# telemetry_box.net
KiCad netlist of a schematic drawn in EAGLE
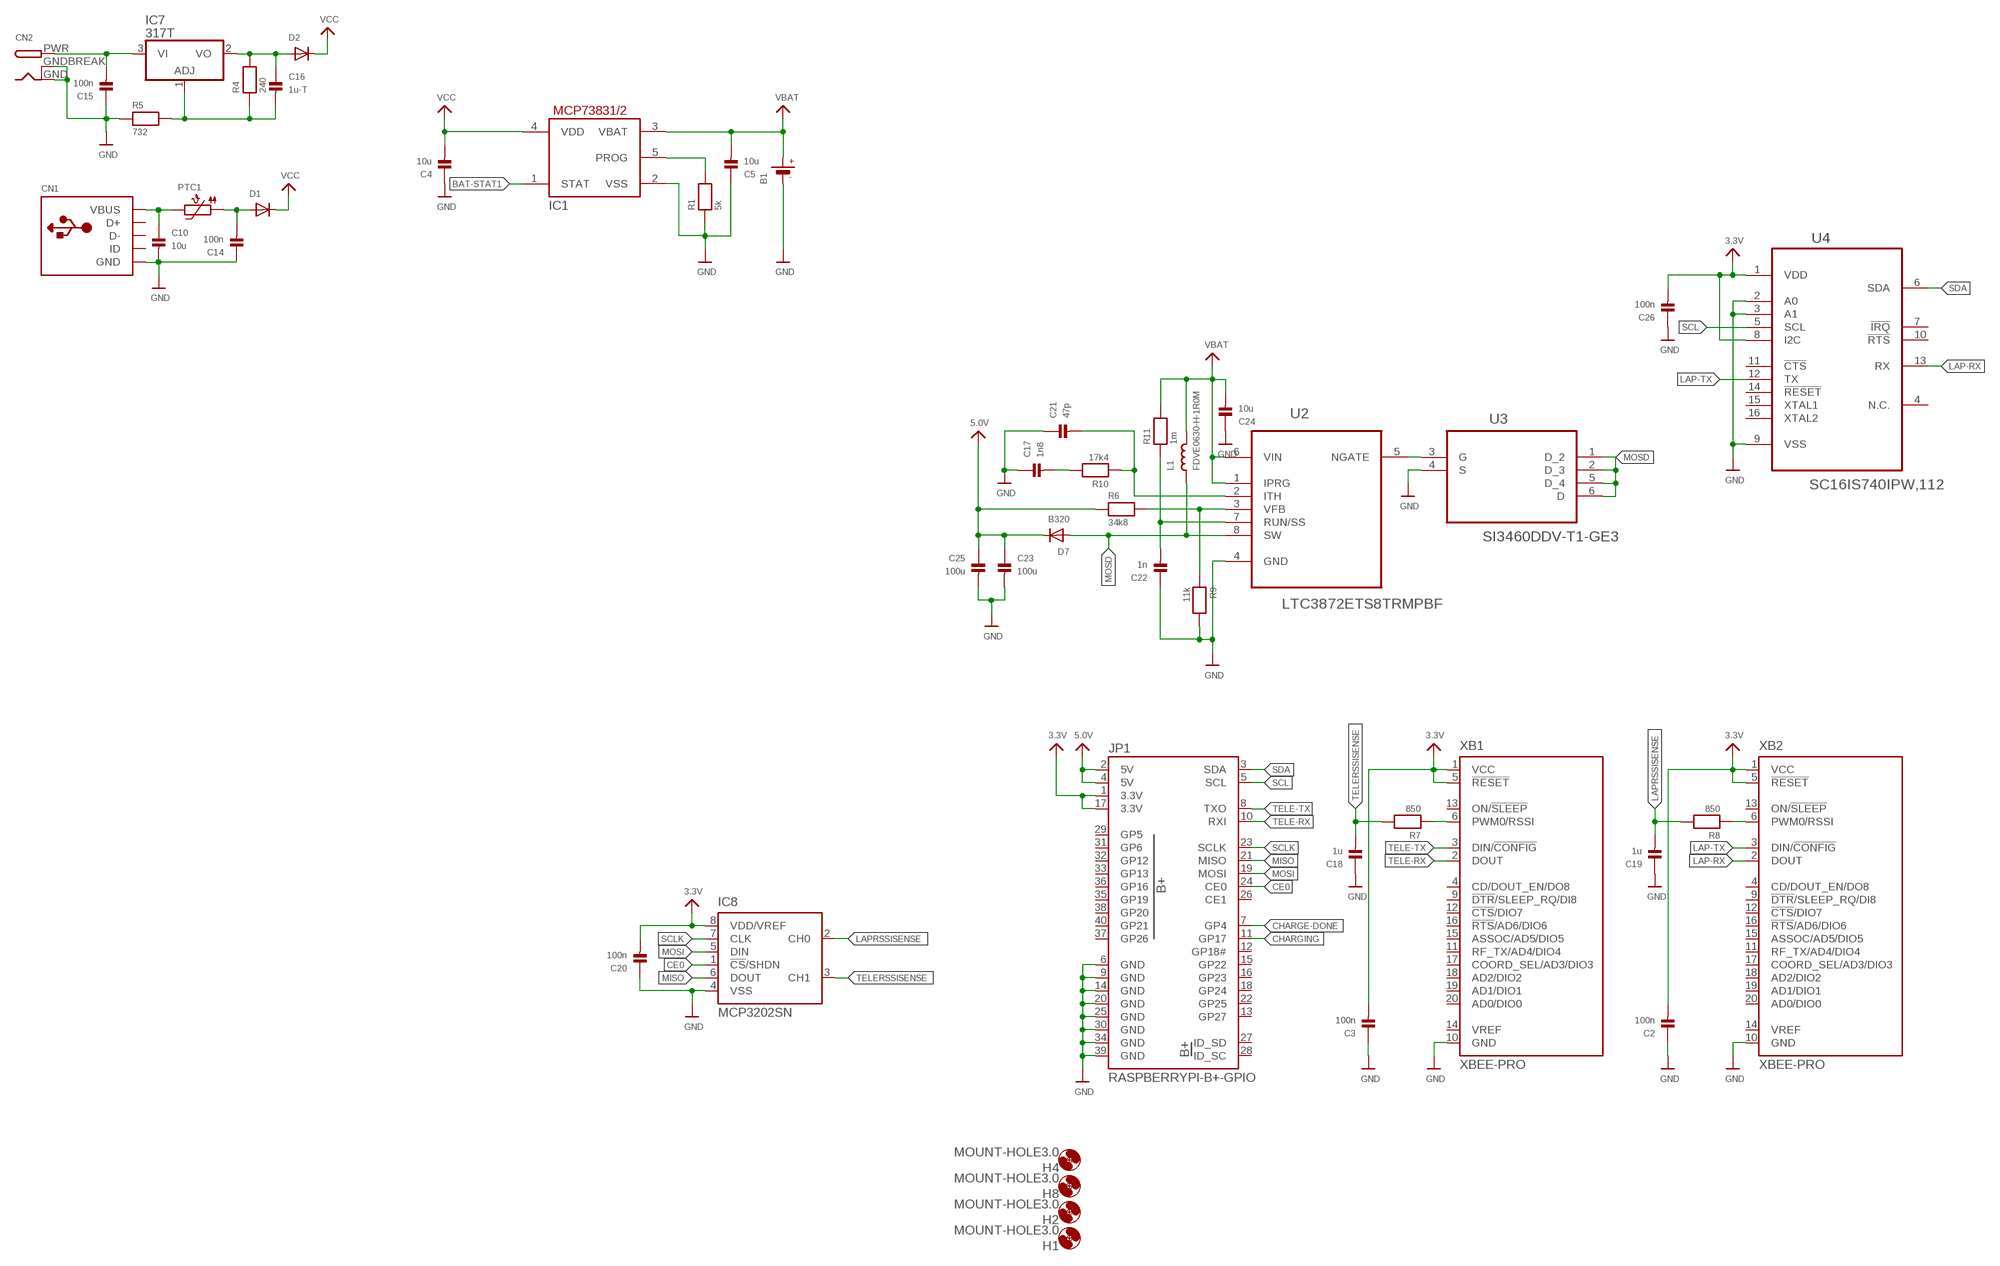
[diagram p0: schematic, sheet 1]

(export (version "E")
  (design (tool "Eeschema 10.0.6"))
  (components
    (comp (ref "B1")
      (value "BATTERY")
      (footprint "eagle-import:JSTPH2")
      (libsource (lib "eagle-import") (part "BATTERY"))
    )
    (comp (ref "C2")
      (value "100n")
      (footprint "eagle-import:_0603")
      (libsource (lib "eagle-import") (part "CAP_CERAMIC_0603"))
    )
    (comp (ref "C3")
      (value "100n")
      (footprint "eagle-import:_0603")
      (libsource (lib "eagle-import") (part "CAP_CERAMIC_0603"))
    )
    (comp (ref "C4")
      (value "10u")
      (footprint "eagle-import:_0805")
      (libsource (lib "eagle-import") (part "CAP_CERAMIC_0805"))
    )
    (comp (ref "C5")
      (value "10u")
      (footprint "eagle-import:_0805")
      (libsource (lib "eagle-import") (part "CAP_CERAMIC_0805"))
    )
    (comp (ref "C10")
      (value "10u")
      (footprint "eagle-import:_0805")
      (libsource (lib "eagle-import") (part "CAP_CERAMIC_0805"))
    )
    (comp (ref "C14")
      (value "100n")
      (footprint "eagle-import:_0603")
      (libsource (lib "eagle-import") (part "CAP_CERAMIC_0603"))
    )
    (comp (ref "C15")
      (value "100n")
      (footprint "eagle-import:_0603")
      (libsource (lib "eagle-import") (part "CAP_CERAMIC_0603"))
    )
    (comp (ref "C16")
      (value "1u-T")
      (footprint "eagle-import:_0603")
      (libsource (lib "eagle-import") (part "CAP_CERAMIC_0603"))
    )
    (comp (ref "C17")
      (value "1n8")
      (footprint "eagle-import:_0603")
      (libsource (lib "eagle-import") (part "CAP_CERAMIC_0603"))
    )
    (comp (ref "C18")
      (value "1u")
      (footprint "eagle-import:_0603")
      (libsource (lib "eagle-import") (part "CAP_CERAMIC_0603"))
    )
    (comp (ref "C19")
      (value "1u")
      (footprint "eagle-import:_0603")
      (libsource (lib "eagle-import") (part "CAP_CERAMIC_0603"))
    )
    (comp (ref "C20")
      (value "100n")
      (footprint "eagle-import:_0603")
      (libsource (lib "eagle-import") (part "CAP_CERAMIC_0603"))
    )
    (comp (ref "C21")
      (value "47p")
      (footprint "eagle-import:_0603")
      (libsource (lib "eagle-import") (part "CAP_CERAMIC_0603"))
    )
    (comp (ref "C22")
      (value "1n")
      (footprint "eagle-import:_0603")
      (libsource (lib "eagle-import") (part "CAP_CERAMIC_0603"))
    )
    (comp (ref "C23")
      (value "100u")
      (footprint "eagle-import:1206")
      (libsource (lib "eagle-import") (part "CAP_CERAMIC1206"))
    )
    (comp (ref "C24")
      (value "10u")
      (footprint "eagle-import:_0805")
      (libsource (lib "eagle-import") (part "CAP_CERAMIC_0805"))
    )
    (comp (ref "C25")
      (value "100u")
      (footprint "eagle-import:1206")
      (libsource (lib "eagle-import") (part "CAP_CERAMIC1206"))
    )
    (comp (ref "C26")
      (value "100n")
      (footprint "eagle-import:_0603")
      (libsource (lib "eagle-import") (part "CAP_CERAMIC_0603"))
    )
    (comp (ref "CN1")
      (value "USBMINIB")
      (footprint "eagle-import:USB-MINIB")
      (libsource (lib "eagle-import") (part "USBMINIB"))
    )
    (comp (ref "CN2")
      (value "DCBARRELPTH")
      (footprint "eagle-import:DCJACK_2MM_PTH")
      (libsource (lib "eagle-import") (part "DCBARRELPTH"))
    )
    (comp (ref "D1")
      (value "DIODESOT23_WAVE")
      (footprint "eagle-import:SOT23-W")
      (libsource (lib "eagle-import") (part "DIODESOT23_WAVE"))
    )
    (comp (ref "D2")
      (value "DIODESOT23_WAVE")
      (footprint "eagle-import:SOT23-W")
      (libsource (lib "eagle-import") (part "DIODESOT23_WAVE"))
    )
    (comp (ref "D7")
      (value "B320")
      (footprint "eagle-import:SMADIODE")
      (libsource (lib "eagle-import") (part "DIODESMA"))
    )
    (comp (ref "H1")
      (value "MOUNT-HOLE3.0")
      (footprint "eagle-import:3,0")
      (libsource (lib "eagle-import") (part "MOUNT-HOLE3.0"))
    )
    (comp (ref "H2")
      (value "MOUNT-HOLE3.0")
      (footprint "eagle-import:3,0")
      (libsource (lib "eagle-import") (part "MOUNT-HOLE3.0"))
    )
    (comp (ref "H4")
      (value "MOUNT-HOLE3.0")
      (footprint "eagle-import:3,0")
      (libsource (lib "eagle-import") (part "MOUNT-HOLE3.0"))
    )
    (comp (ref "H8")
      (value "MOUNT-HOLE3.0")
      (footprint "eagle-import:3,0")
      (libsource (lib "eagle-import") (part "MOUNT-HOLE3.0"))
    )
    (comp (ref "IC1")
      (value "MCP73831/OT")
      (footprint "eagle-import:SOT23-5L")
      (libsource (lib "eagle-import") (part "MCP73831/OT"))
    )
    (comp (ref "IC7")
      (value "317T")
      (footprint "eagle-import:TO220H")
      (libsource (lib "eagle-import") (part "317T"))
    )
    (comp (ref "IC8")
      (value "MCP3202SN")
      (footprint "eagle-import:SO-08")
      (fields (field (name "MF") "MICROCHIP") (field (name "MPN") "MCP3202-CI/SN"))
      (libsource (lib "eagle-import") (part "MCP3202SN"))
    )
    (comp (ref "JP1")
      (value "RASPBERRYPI-B+-GPIO")
      (footprint "eagle-import:2X20-SHROUDED")
      (libsource (lib "eagle-import") (part "RASPBERRYPI-B+-GPIO"))
    )
    (comp (ref "L1")
      (value "FDVE0630-H-1R0M")
      (footprint "eagle-import:INDUCTOR_6X6MM_TDK_SLF6045")
      (libsource (lib "eagle-import") (part "INDUCTORTDK_SLF6045"))
    )
    (comp (ref "PTC1")
      (value "PTC1206")
      (footprint "eagle-import:1206")
      (libsource (lib "eagle-import") (part "PTC1206"))
    )
    (comp (ref "R1")
      (value "5k")
      (footprint "eagle-import:_0603")
      (libsource (lib "eagle-import") (part "RESISTOR_0603"))
    )
    (comp (ref "R4")
      (value "240")
      (footprint "eagle-import:_0603")
      (libsource (lib "eagle-import") (part "RESISTOR_0603"))
    )
    (comp (ref "R5")
      (value "732")
      (footprint "eagle-import:_0603")
      (libsource (lib "eagle-import") (part "RESISTOR_0603"))
    )
    (comp (ref "R6")
      (value "34k8")
      (footprint "eagle-import:_0603")
      (libsource (lib "eagle-import") (part "RESISTOR_0603"))
    )
    (comp (ref "R7")
      (value "850")
      (footprint "eagle-import:_0603")
      (libsource (lib "eagle-import") (part "RESISTOR_0603"))
    )
    (comp (ref "R8")
      (value "850")
      (footprint "eagle-import:_0603")
      (libsource (lib "eagle-import") (part "RESISTOR_0603"))
    )
    (comp (ref "R9")
      (value "11k")
      (footprint "eagle-import:_0603")
      (libsource (lib "eagle-import") (part "RESISTOR_0603"))
    )
    (comp (ref "R10")
      (value "17k4")
      (footprint "eagle-import:_0603")
      (libsource (lib "eagle-import") (part "RESISTOR_0603"))
    )
    (comp (ref "R11")
      (value "1m")
      (footprint "eagle-import:_0603")
      (libsource (lib "eagle-import") (part "RESISTOR_0603"))
    )
    (comp (ref "U2")
      (value "LTC3872ETS8TRMPBF")
      (footprint "eagle-import:SOT65P280X100-8N")
      (fields (field (name "MPN") "LTC3872ETS8#TRMPBF"))
      (libsource (lib "eagle-import") (part "LTC3872ETS8TRMPBF"))
    )
    (comp (ref "U3")
      (value "SI3460DDV-T1-GE3")
      (footprint "eagle-import:SOT95P285X110-6N")
      (fields (field (name "MPN") "SI3457CDV-T1-GE3"))
      (libsource (lib "eagle-import") (part "SI3457CDV-T1-GE3"))
    )
    (comp (ref "U4")
      (value "SC16IS740IPW,112")
      (footprint "eagle-import:SOP65P640X110-16N")
      (libsource (lib "eagle-import") (part "SC16IS740IPW,112"))
    )
    (comp (ref "XB1")
      (value "XBEE-PRO")
      (footprint "eagle-import:XBEE-PRO")
      (libsource (lib "eagle-import") (part "XBEE-PRO"))
    )
    (comp (ref "XB2")
      (value "XBEE-PRO")
      (footprint "eagle-import:XBEE-PRO")
      (libsource (lib "eagle-import") (part "XBEE-PRO"))
    )
  )
  (nets
    (net (code "1") (name "3.3V") (class "Default")
      (node (ref "C2") (pin "2") (pinfunction "P$2_2") (pintype "passive"))
      (node (ref "C20") (pin "2") (pinfunction "P$2_2") (pintype "passive"))
      (node (ref "C26") (pin "2") (pinfunction "P$2_2") (pintype "passive"))
      (node (ref "C3") (pin "2") (pinfunction "P$2_2") (pintype "passive"))
      (node (ref "IC8") (pin "8") (pinfunction "VDD/VREF_8") (pintype "input"))
      (node (ref "JP1") (pin "1") (pinfunction "3.3V_1") (pintype "power_in"))
      (node (ref "JP1") (pin "17") (pinfunction "3.3V_17") (pintype "power_in"))
      (node (ref "U4") (pin "1") (pinfunction "VDD_1") (pintype "power_in"))
      (node (ref "U4") (pin "8") (pinfunction "I2C_8") (pintype "input"))
      (node (ref "XB1") (pin "1") (pinfunction "VCC_1") (pintype "power_in"))
      (node (ref "XB1") (pin "5") (pinfunction "~{RESET}_5") (pintype "input"))
      (node (ref "XB2") (pin "1") (pinfunction "VCC_1") (pintype "power_in"))
      (node (ref "XB2") (pin "5") (pinfunction "~{RESET}_5") (pintype "input"))
    )
    (net (code "2") (name "5.0V") (class "Default")
      (node (ref "C23") (pin "1") (pinfunction "P$1_1") (pintype "passive"))
      (node (ref "C25") (pin "1") (pinfunction "P$1_1") (pintype "passive"))
      (node (ref "D7") (pin "C") (pinfunction "C_C") (pintype "passive"))
      (node (ref "JP1") (pin "2") (pinfunction "5V_2") (pintype "power_in"))
      (node (ref "JP1") (pin "4") (pinfunction "5V_4") (pintype "power_in"))
      (node (ref "R6") (pin "1") (pinfunction "1_1") (pintype "passive"))
    )
    (net (code "3") (name "BAT-STAT1") (class "Default")
      (node (ref "IC1") (pin "1") (pinfunction "STAT_1") (pintype "output"))
    )
    (net (code "4") (name "CE0") (class "Default")
      (node (ref "IC8") (pin "1") (pinfunction "~{CS}/SHDN_1") (pintype "input"))
      (node (ref "JP1") (pin "24") (pinfunction "CE0_24") (pintype "output"))
    )
    (net (code "5") (name "CHARGE-DONE") (class "Default")
      (node (ref "JP1") (pin "7") (pinfunction "GP4_7") (pintype "bidirectional"))
    )
    (net (code "6") (name "CHARGING") (class "Default")
      (node (ref "JP1") (pin "11") (pinfunction "GP17_11") (pintype "bidirectional"))
    )
    (net (code "7") (name "GND") (class "Default")
      (node (ref "B1") (pin "1") (pinfunction "-_1") (pintype "passive"))
      (node (ref "C10") (pin "2") (pinfunction "P$2_2") (pintype "passive"))
      (node (ref "C14") (pin "1") (pinfunction "P$1_1") (pintype "passive"))
      (node (ref "C15") (pin "1") (pinfunction "P$1_1") (pintype "passive"))
      (node (ref "C17") (pin "1") (pinfunction "P$1_1") (pintype "passive"))
      (node (ref "C18") (pin "1") (pinfunction "P$1_1") (pintype "passive"))
      (node (ref "C19") (pin "1") (pinfunction "P$1_1") (pintype "passive"))
      (node (ref "C2") (pin "1") (pinfunction "P$1_1") (pintype "passive"))
      (node (ref "C20") (pin "1") (pinfunction "P$1_1") (pintype "passive"))
      (node (ref "C21") (pin "1") (pinfunction "P$1_1") (pintype "passive"))
      (node (ref "C22") (pin "1") (pinfunction "P$1_1") (pintype "passive"))
      (node (ref "C23") (pin "2") (pinfunction "P$2_2") (pintype "passive"))
      (node (ref "C24") (pin "1") (pinfunction "P$1_1") (pintype "passive"))
      (node (ref "C25") (pin "2") (pinfunction "P$2_2") (pintype "passive"))
      (node (ref "C26") (pin "1") (pinfunction "P$1_1") (pintype "passive"))
      (node (ref "C3") (pin "1") (pinfunction "P$1_1") (pintype "passive"))
      (node (ref "C4") (pin "1") (pinfunction "P$1_1") (pintype "passive"))
      (node (ref "C5") (pin "1") (pinfunction "P$1_1") (pintype "passive"))
      (node (ref "CN1") (pin "GND") (pinfunction "GND_GND") (pintype "power_in"))
      (node (ref "CN2") (pin "GND") (pinfunction "GND_GND") (pintype "power_in"))
      (node (ref "CN2") (pin "GNDBREAK") (pinfunction "GNDBREAK_GNDBREAK") (pintype "power_in"))
      (node (ref "IC1") (pin "2") (pinfunction "VSS_2") (pintype "power_in"))
      (node (ref "IC8") (pin "4") (pinfunction "VSS_4") (pintype "input"))
      (node (ref "JP1") (pin "14") (pinfunction "GND_14") (pintype "power_in"))
      (node (ref "JP1") (pin "20") (pinfunction "GND_20") (pintype "power_in"))
      (node (ref "JP1") (pin "25") (pinfunction "GND_25") (pintype "power_in"))
      (node (ref "JP1") (pin "30") (pinfunction "GND_30") (pintype "power_in"))
      (node (ref "JP1") (pin "34") (pinfunction "GND_34") (pintype "power_in"))
      (node (ref "JP1") (pin "39") (pinfunction "GND_39") (pintype "power_in"))
      (node (ref "JP1") (pin "6") (pinfunction "GND_6") (pintype "power_in"))
      (node (ref "JP1") (pin "9") (pinfunction "GND_9") (pintype "power_in"))
      (node (ref "R1") (pin "1") (pinfunction "1_1") (pintype "passive"))
      (node (ref "R5") (pin "1") (pinfunction "1_1") (pintype "passive"))
      (node (ref "R9") (pin "2") (pinfunction "2_2") (pintype "passive"))
      (node (ref "U2") (pin "4") (pinfunction "GND_4") (pintype "passive"))
      (node (ref "U3") (pin "4") (pinfunction "S_4") (pintype "passive"))
      (node (ref "U4") (pin "2") (pinfunction "A0_2") (pintype "input"))
      (node (ref "U4") (pin "3") (pinfunction "A1_3") (pintype "input"))
      (node (ref "U4") (pin "9") (pinfunction "VSS_9") (pintype "power_in"))
      (node (ref "XB1") (pin "10") (pinfunction "GND_10") (pintype "power_in"))
      (node (ref "XB2") (pin "10") (pinfunction "GND_10") (pintype "power_in"))
    )
    (net (code "8") (name "LAP-RX") (class "Default")
      (node (ref "U4") (pin "13") (pinfunction "RX_13") (pintype "output"))
      (node (ref "XB2") (pin "2") (pinfunction "DOUT_2") (pintype "output"))
    )
    (net (code "9") (name "LAP-TX") (class "Default")
      (node (ref "U4") (pin "12") (pinfunction "TX_12") (pintype "input"))
      (node (ref "XB2") (pin "3") (pinfunction "DIN/~{CONFIG}_3") (pintype "input"))
    )
    (net (code "10") (name "LAPRSSISENSE") (class "Default")
      (node (ref "C19") (pin "2") (pinfunction "P$2_2") (pintype "passive"))
      (node (ref "IC8") (pin "2") (pinfunction "CH0_2") (pintype "input"))
      (node (ref "R8") (pin "2") (pinfunction "2_2") (pintype "passive"))
    )
    (net (code "11") (name "MISO") (class "Default")
      (node (ref "IC8") (pin "6") (pinfunction "DOUT_6") (pintype "input"))
      (node (ref "JP1") (pin "21") (pinfunction "MISO_21") (pintype "input"))
    )
    (net (code "12") (name "MOSD") (class "Default")
      (node (ref "D7") (pin "A") (pinfunction "A_A") (pintype "passive"))
      (node (ref "L1") (pin "P$1") (pinfunction "1_P$1") (pintype "passive"))
      (node (ref "U2") (pin "8") (pinfunction "SW_8") (pintype "passive"))
      (node (ref "U3") (pin "1") (pinfunction "D_2_1") (pintype "passive"))
      (node (ref "U3") (pin "2") (pinfunction "D_3_2") (pintype "passive"))
      (node (ref "U3") (pin "5") (pinfunction "D_4_5") (pintype "passive"))
      (node (ref "U3") (pin "6") (pinfunction "D_6") (pintype "passive"))
    )
    (net (code "13") (name "MOSI") (class "Default")
      (node (ref "IC8") (pin "5") (pinfunction "DIN_5") (pintype "input"))
      (node (ref "JP1") (pin "19") (pinfunction "MOSI_19") (pintype "output"))
    )
    (net (code "14") (name "Net-(C10-P$1)") (class "Default")
      (node (ref "C10") (pin "1") (pinfunction "P$1_1") (pintype "passive"))
      (node (ref "CN1") (pin "VBUS") (pinfunction "VBUS_VBUS") (pintype "power_in"))
      (node (ref "PTC1") (pin "2") (pinfunction "2_2") (pintype "passive"))
    )
    (net (code "15") (name "Net-(C14-P$2)") (class "Default")
      (node (ref "C14") (pin "2") (pinfunction "P$2_2") (pintype "passive"))
      (node (ref "D1") (pin "1") (pinfunction "A_1") (pintype "passive"))
      (node (ref "PTC1") (pin "1") (pinfunction "1_1") (pintype "passive"))
    )
    (net (code "16") (name "Net-(C15-P$2)") (class "Default")
      (node (ref "C15") (pin "2") (pinfunction "P$2_2") (pintype "passive"))
      (node (ref "CN2") (pin "PWR") (pinfunction "PWR_PWR") (pintype "power_in"))
      (node (ref "IC7") (pin "3") (pinfunction "VI_3") (pintype "input"))
    )
    (net (code "17") (name "Net-(C16-P$1)") (class "Default")
      (node (ref "C16") (pin "1") (pinfunction "P$1_1") (pintype "passive"))
      (node (ref "D2") (pin "1") (pinfunction "A_1") (pintype "passive"))
      (node (ref "IC7") (pin "2") (pinfunction "VO_2") (pintype "passive"))
      (node (ref "R4") (pin "2") (pinfunction "2_2") (pintype "passive"))
    )
    (net (code "18") (name "Net-(C16-P$2)") (class "Default")
      (node (ref "C16") (pin "2") (pinfunction "P$2_2") (pintype "passive"))
      (node (ref "IC7") (pin "1") (pinfunction "ADJ_1") (pintype "input"))
      (node (ref "R4") (pin "1") (pinfunction "1_1") (pintype "passive"))
      (node (ref "R5") (pin "2") (pinfunction "2_2") (pintype "passive"))
    )
    (net (code "19") (name "Net-(C17-P$2)") (class "Default")
      (node (ref "C17") (pin "2") (pinfunction "P$2_2") (pintype "passive"))
      (node (ref "R10") (pin "2") (pinfunction "2_2") (pintype "passive"))
    )
    (net (code "20") (name "Net-(C21-P$2)") (class "Default")
      (node (ref "C21") (pin "2") (pinfunction "P$2_2") (pintype "passive"))
      (node (ref "R10") (pin "1") (pinfunction "1_1") (pintype "passive"))
      (node (ref "U2") (pin "2") (pinfunction "ITH_2") (pintype "input"))
    )
    (net (code "21") (name "Net-(C22-P$2)") (class "Default")
      (node (ref "C22") (pin "2") (pinfunction "P$2_2") (pintype "passive"))
      (node (ref "R11") (pin "1") (pinfunction "1_1") (pintype "passive"))
      (node (ref "U2") (pin "7") (pinfunction "RUN/SS_7") (pintype "input"))
    )
    (net (code "22") (name "Net-(IC1-PROG)") (class "Default")
      (node (ref "IC1") (pin "5") (pinfunction "PROG_5") (pintype "input"))
      (node (ref "R1") (pin "2") (pinfunction "2_2") (pintype "passive"))
    )
    (net (code "23") (name "Net-(U2-NGATE)") (class "Default")
      (node (ref "U2") (pin "5") (pinfunction "NGATE_5") (pintype "output"))
      (node (ref "U3") (pin "3") (pinfunction "G_3") (pintype "passive"))
    )
    (net (code "24") (name "Net-(U2-VFB)") (class "Default")
      (node (ref "R6") (pin "2") (pinfunction "2_2") (pintype "passive"))
      (node (ref "R9") (pin "1") (pinfunction "1_1") (pintype "passive"))
      (node (ref "U2") (pin "3") (pinfunction "VFB_3") (pintype "input"))
    )
    (net (code "25") (name "Net-(XB1-PWM0{slash}RSSI)") (class "Default")
      (node (ref "R7") (pin "1") (pinfunction "1_1") (pintype "passive"))
      (node (ref "XB1") (pin "6") (pinfunction "PWM0/RSSI_6") (pintype "output"))
    )
    (net (code "26") (name "Net-(XB2-PWM0{slash}RSSI)") (class "Default")
      (node (ref "R8") (pin "1") (pinfunction "1_1") (pintype "passive"))
      (node (ref "XB2") (pin "6") (pinfunction "PWM0/RSSI_6") (pintype "output"))
    )
    (net (code "27") (name "SCL") (class "Default")
      (node (ref "JP1") (pin "5") (pinfunction "SCL_5") (pintype "bidirectional"))
      (node (ref "U4") (pin "5") (pinfunction "SCL_5") (pintype "input"))
    )
    (net (code "28") (name "SCLK") (class "Default")
      (node (ref "IC8") (pin "7") (pinfunction "CLK_7") (pintype "input"))
      (node (ref "JP1") (pin "23") (pinfunction "SCLK_23") (pintype "output"))
    )
    (net (code "29") (name "SDA") (class "Default")
      (node (ref "JP1") (pin "3") (pinfunction "SDA_3") (pintype "bidirectional"))
      (node (ref "U4") (pin "6") (pinfunction "SDA_6") (pintype "bidirectional"))
    )
    (net (code "30") (name "TELE-RX") (class "Default")
      (node (ref "JP1") (pin "10") (pinfunction "RXI_10") (pintype "input"))
      (node (ref "XB1") (pin "2") (pinfunction "DOUT_2") (pintype "output"))
    )
    (net (code "31") (name "TELE-TX") (class "Default")
      (node (ref "JP1") (pin "8") (pinfunction "TXO_8") (pintype "output"))
      (node (ref "XB1") (pin "3") (pinfunction "DIN/~{CONFIG}_3") (pintype "input"))
    )
    (net (code "32") (name "TELERSSISENSE") (class "Default")
      (node (ref "C18") (pin "2") (pinfunction "P$2_2") (pintype "passive"))
      (node (ref "IC8") (pin "3") (pinfunction "CH1_3") (pintype "input"))
      (node (ref "R7") (pin "2") (pinfunction "2_2") (pintype "passive"))
    )
    (net (code "33") (name "VBAT") (class "Default")
      (node (ref "B1") (pin "2") (pinfunction "+_2") (pintype "passive"))
      (node (ref "C24") (pin "2") (pinfunction "P$2_2") (pintype "passive"))
      (node (ref "C5") (pin "2") (pinfunction "P$2_2") (pintype "passive"))
      (node (ref "IC1") (pin "3") (pinfunction "VBAT_3") (pintype "bidirectional"))
      (node (ref "L1") (pin "P$2") (pinfunction "2_P$2") (pintype "passive"))
      (node (ref "R11") (pin "2") (pinfunction "2_2") (pintype "passive"))
      (node (ref "U2") (pin "1") (pinfunction "IPRG_1") (pintype "input"))
      (node (ref "U2") (pin "6") (pinfunction "VIN_6") (pintype "power_in"))
    )
    (net (code "34") (name "VCC") (class "Default")
      (node (ref "C4") (pin "2") (pinfunction "P$2_2") (pintype "passive"))
      (node (ref "D1") (pin "3") (pinfunction "C_3") (pintype "passive"))
      (node (ref "D2") (pin "3") (pinfunction "C_3") (pintype "passive"))
      (node (ref "IC1") (pin "4") (pinfunction "VDD_4") (pintype "power_in"))
    )
    (net (code "35") (name "unconnected-(CN1-PadD+)") (class "Default")
      (node (ref "CN1") (pin "D+") (pinfunction "D+_D+") (pintype "bidirectional"))
    )
    (net (code "36") (name "unconnected-(CN1-PadD-)") (class "Default")
      (node (ref "CN1") (pin "D-") (pinfunction "D-_D-") (pintype "bidirectional"))
    )
    (net (code "37") (name "unconnected-(CN1-PadID)") (class "Default")
      (node (ref "CN1") (pin "ID") (pinfunction "ID_ID") (pintype "bidirectional"))
    )
    (net (code "38") (name "unconnected-(JP1-CE1-Pad26)") (class "Default")
      (node (ref "JP1") (pin "26") (pinfunction "CE1_26") (pintype "output"))
    )
    (net (code "39") (name "unconnected-(JP1-GP5-Pad29)") (class "Default")
      (node (ref "JP1") (pin "29") (pinfunction "GP5_29") (pintype "bidirectional"))
    )
    (net (code "40") (name "unconnected-(JP1-GP6-Pad31)") (class "Default")
      (node (ref "JP1") (pin "31") (pinfunction "GP6_31") (pintype "bidirectional"))
    )
    (net (code "41") (name "unconnected-(JP1-GP12-Pad32)") (class "Default")
      (node (ref "JP1") (pin "32") (pinfunction "GP12_32") (pintype "bidirectional"))
    )
    (net (code "42") (name "unconnected-(JP1-GP13-Pad33)") (class "Default")
      (node (ref "JP1") (pin "33") (pinfunction "GP13_33") (pintype "bidirectional"))
    )
    (net (code "43") (name "unconnected-(JP1-GP16-Pad36)") (class "Default")
      (node (ref "JP1") (pin "36") (pinfunction "GP16_36") (pintype "bidirectional"))
    )
    (net (code "44") (name "unconnected-(JP1-GP18#-Pad12)") (class "Default")
      (node (ref "JP1") (pin "12") (pinfunction "GP18#_12") (pintype "bidirectional"))
    )
    (net (code "45") (name "unconnected-(JP1-GP19-Pad35)") (class "Default")
      (node (ref "JP1") (pin "35") (pinfunction "GP19_35") (pintype "bidirectional"))
    )
    (net (code "46") (name "unconnected-(JP1-GP20-Pad38)") (class "Default")
      (node (ref "JP1") (pin "38") (pinfunction "GP20_38") (pintype "bidirectional"))
    )
    (net (code "47") (name "unconnected-(JP1-GP21-Pad40)") (class "Default")
      (node (ref "JP1") (pin "40") (pinfunction "GP21_40") (pintype "bidirectional"))
    )
    (net (code "48") (name "unconnected-(JP1-GP22-Pad15)") (class "Default")
      (node (ref "JP1") (pin "15") (pinfunction "GP22_15") (pintype "bidirectional"))
    )
    (net (code "49") (name "unconnected-(JP1-GP23-Pad16)") (class "Default")
      (node (ref "JP1") (pin "16") (pinfunction "GP23_16") (pintype "bidirectional"))
    )
    (net (code "50") (name "unconnected-(JP1-GP24-Pad18)") (class "Default")
      (node (ref "JP1") (pin "18") (pinfunction "GP24_18") (pintype "bidirectional"))
    )
    (net (code "51") (name "unconnected-(JP1-GP25-Pad22)") (class "Default")
      (node (ref "JP1") (pin "22") (pinfunction "GP25_22") (pintype "bidirectional"))
    )
    (net (code "52") (name "unconnected-(JP1-GP26-Pad37)") (class "Default")
      (node (ref "JP1") (pin "37") (pinfunction "GP26_37") (pintype "bidirectional"))
    )
    (net (code "53") (name "unconnected-(JP1-GP27-Pad13)") (class "Default")
      (node (ref "JP1") (pin "13") (pinfunction "GP27_13") (pintype "bidirectional"))
    )
    (net (code "54") (name "unconnected-(JP1-ID_SC-Pad28)") (class "Default")
      (node (ref "JP1") (pin "28") (pinfunction "ID_SC_28") (pintype "bidirectional"))
    )
    (net (code "55") (name "unconnected-(JP1-ID_SD-Pad27)") (class "Default")
      (node (ref "JP1") (pin "27") (pinfunction "ID_SD_27") (pintype "bidirectional"))
    )
    (net (code "56") (name "unconnected-(U4-N.C.-Pad4)") (class "Default")
      (node (ref "U4") (pin "4") (pinfunction "N.C._4") (pintype "no_connect"))
    )
    (net (code "57") (name "unconnected-(U4-XTAL1-Pad15)") (class "Default")
      (node (ref "U4") (pin "15") (pinfunction "XTAL1_15") (pintype "input"))
    )
    (net (code "58") (name "unconnected-(U4-XTAL2-Pad16)") (class "Default")
      (node (ref "U4") (pin "16") (pinfunction "XTAL2_16") (pintype "output"))
    )
    (net (code "59") (name "unconnected-(U4-~{CTS}-Pad11)") (class "Default")
      (node (ref "U4") (pin "11") (pinfunction "~{CTS}_11") (pintype "input"))
    )
    (net (code "60") (name "unconnected-(U4-~{IRQ}-Pad7)") (class "Default")
      (node (ref "U4") (pin "7") (pinfunction "~{IRQ}_7") (pintype "output"))
    )
    (net (code "61") (name "unconnected-(U4-~{RESET}-Pad14)") (class "Default")
      (node (ref "U4") (pin "14") (pinfunction "~{RESET}_14") (pintype "input"))
    )
    (net (code "62") (name "unconnected-(U4-~{RTS}-Pad10)") (class "Default")
      (node (ref "U4") (pin "10") (pinfunction "~{RTS}_10") (pintype "output"))
    )
    (net (code "63") (name "unconnected-(XB1-AD0{slash}DIO0-Pad20)") (class "Default")
      (node (ref "XB1") (pin "20") (pinfunction "AD0/DIO0_20") (pintype "bidirectional"))
    )
    (net (code "64") (name "unconnected-(XB1-AD1{slash}DIO1-Pad19)") (class "Default")
      (node (ref "XB1") (pin "19") (pinfunction "AD1/DIO1_19") (pintype "bidirectional"))
    )
    (net (code "65") (name "unconnected-(XB1-AD2{slash}DIO2-Pad18)") (class "Default")
      (node (ref "XB1") (pin "18") (pinfunction "AD2/DIO2_18") (pintype "bidirectional"))
    )
    (net (code "66") (name "unconnected-(XB1-ASSOC{slash}AD5{slash}DIO5-Pad15)") (class "Default")
      (node (ref "XB1") (pin "15") (pinfunction "ASSOC/AD5/DIO5_15") (pintype "bidirectional"))
    )
    (net (code "67") (name "unconnected-(XB1-CD{slash}DOUT_EN{slash}DO8-Pad4)") (class "Default")
      (node (ref "XB1") (pin "4") (pinfunction "CD/DOUT_EN/DO8_4") (pintype "output"))
    )
    (net (code "68") (name "unconnected-(XB1-COORD_SEL{slash}AD3{slash}DIO3-Pad17)") (class "Default")
      (node (ref "XB1") (pin "17") (pinfunction "COORD_SEL/AD3/DIO3_17") (pintype "bidirectional"))
    )
    (net (code "69") (name "unconnected-(XB1-ON{slash}~{SLEEP}-Pad13)") (class "Default")
      (node (ref "XB1") (pin "13") (pinfunction "ON/~{SLEEP}_13") (pintype "output"))
    )
    (net (code "70") (name "unconnected-(XB1-RF_TX{slash}AD4{slash}DIO4-Pad11)") (class "Default")
      (node (ref "XB1") (pin "11") (pinfunction "RF_TX/AD4/DIO4_11") (pintype "bidirectional"))
    )
    (net (code "71") (name "unconnected-(XB1-VREF-Pad14)") (class "Default")
      (node (ref "XB1") (pin "14") (pinfunction "VREF_14") (pintype "input"))
    )
    (net (code "72") (name "unconnected-(XB1-~{CTS}{slash}DIO7-Pad12)") (class "Default")
      (node (ref "XB1") (pin "12") (pinfunction "~{CTS}/DIO7_12") (pintype "bidirectional"))
    )
    (net (code "73") (name "unconnected-(XB1-~{DTR}{slash}SLEEP_RQ{slash}DI8-Pad9)") (class "Default")
      (node (ref "XB1") (pin "9") (pinfunction "~{DTR}/SLEEP_RQ/DI8_9") (pintype "bidirectional"))
    )
    (net (code "74") (name "unconnected-(XB1-~{RTS}{slash}AD6{slash}DIO6-Pad16)") (class "Default")
      (node (ref "XB1") (pin "16") (pinfunction "~{RTS}/AD6/DIO6_16") (pintype "bidirectional"))
    )
    (net (code "75") (name "unconnected-(XB2-AD0{slash}DIO0-Pad20)") (class "Default")
      (node (ref "XB2") (pin "20") (pinfunction "AD0/DIO0_20") (pintype "bidirectional"))
    )
    (net (code "76") (name "unconnected-(XB2-AD1{slash}DIO1-Pad19)") (class "Default")
      (node (ref "XB2") (pin "19") (pinfunction "AD1/DIO1_19") (pintype "bidirectional"))
    )
    (net (code "77") (name "unconnected-(XB2-AD2{slash}DIO2-Pad18)") (class "Default")
      (node (ref "XB2") (pin "18") (pinfunction "AD2/DIO2_18") (pintype "bidirectional"))
    )
    (net (code "78") (name "unconnected-(XB2-ASSOC{slash}AD5{slash}DIO5-Pad15)") (class "Default")
      (node (ref "XB2") (pin "15") (pinfunction "ASSOC/AD5/DIO5_15") (pintype "bidirectional"))
    )
    (net (code "79") (name "unconnected-(XB2-CD{slash}DOUT_EN{slash}DO8-Pad4)") (class "Default")
      (node (ref "XB2") (pin "4") (pinfunction "CD/DOUT_EN/DO8_4") (pintype "output"))
    )
    (net (code "80") (name "unconnected-(XB2-COORD_SEL{slash}AD3{slash}DIO3-Pad17)") (class "Default")
      (node (ref "XB2") (pin "17") (pinfunction "COORD_SEL/AD3/DIO3_17") (pintype "bidirectional"))
    )
    (net (code "81") (name "unconnected-(XB2-ON{slash}~{SLEEP}-Pad13)") (class "Default")
      (node (ref "XB2") (pin "13") (pinfunction "ON/~{SLEEP}_13") (pintype "output"))
    )
    (net (code "82") (name "unconnected-(XB2-RF_TX{slash}AD4{slash}DIO4-Pad11)") (class "Default")
      (node (ref "XB2") (pin "11") (pinfunction "RF_TX/AD4/DIO4_11") (pintype "bidirectional"))
    )
    (net (code "83") (name "unconnected-(XB2-VREF-Pad14)") (class "Default")
      (node (ref "XB2") (pin "14") (pinfunction "VREF_14") (pintype "input"))
    )
    (net (code "84") (name "unconnected-(XB2-~{CTS}{slash}DIO7-Pad12)") (class "Default")
      (node (ref "XB2") (pin "12") (pinfunction "~{CTS}/DIO7_12") (pintype "bidirectional"))
    )
    (net (code "85") (name "unconnected-(XB2-~{DTR}{slash}SLEEP_RQ{slash}DI8-Pad9)") (class "Default")
      (node (ref "XB2") (pin "9") (pinfunction "~{DTR}/SLEEP_RQ/DI8_9") (pintype "bidirectional"))
    )
    (net (code "86") (name "unconnected-(XB2-~{RTS}{slash}AD6{slash}DIO6-Pad16)") (class "Default")
      (node (ref "XB2") (pin "16") (pinfunction "~{RTS}/AD6/DIO6_16") (pintype "bidirectional"))
    )
  )
)
